# ratatouille.net
KiCad netlist of a schematic drawn in EAGLE
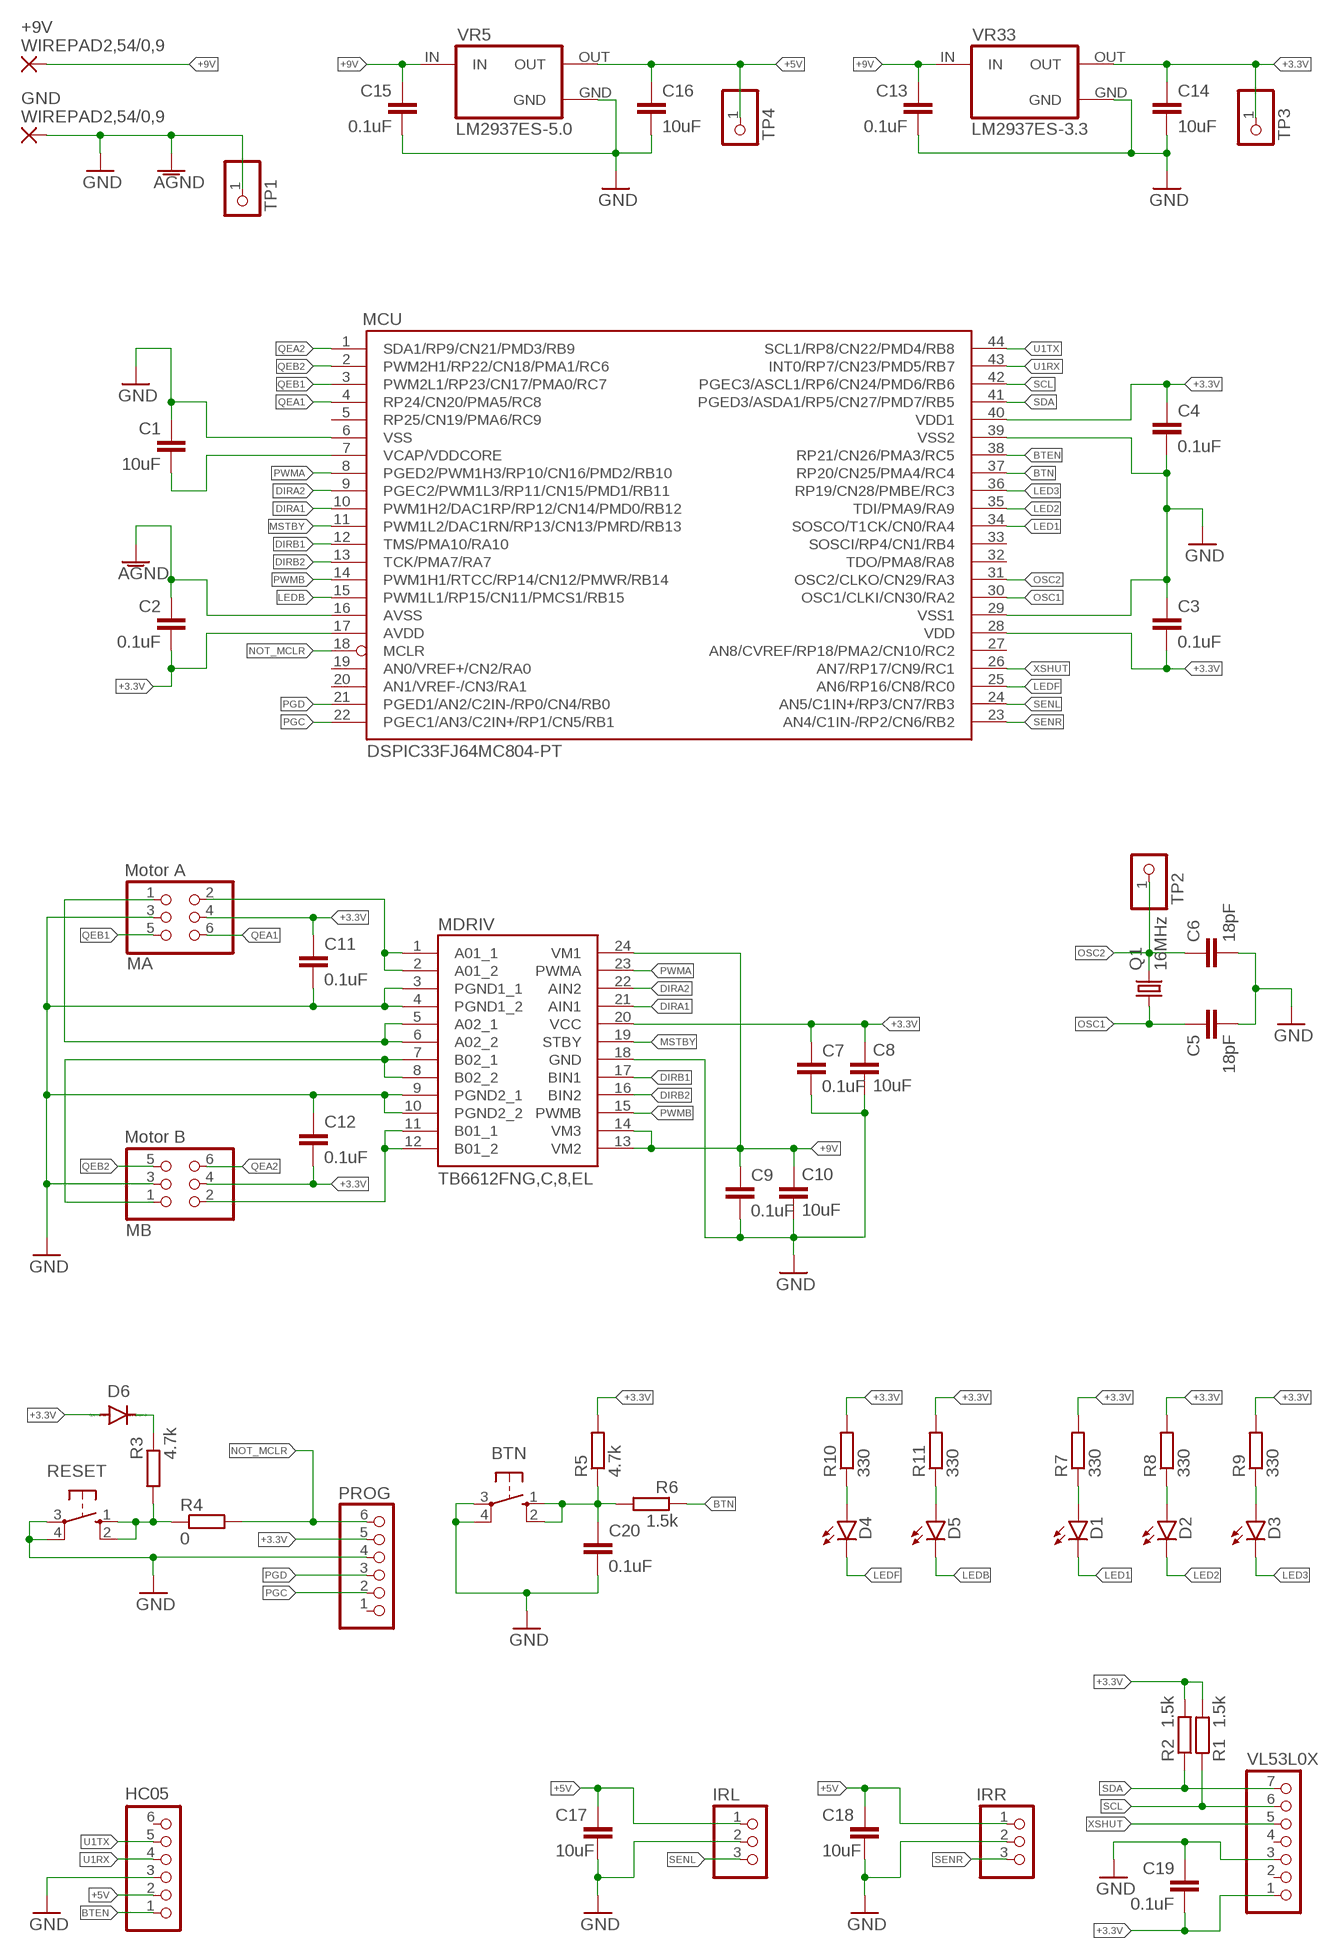
[diagram p0: schematic, sheet 1]

(export (version "E")
  (design (tool "Eeschema 10.0.6"))
  (components
    (comp (ref "+9V")
      (value "WIREPAD2,54/0,9")
      (footprint "eagle-import:2,54_0,9")
      (libsource (lib "eagle-import") (part "WIREPAD2,54/0,9"))
    )
    (comp (ref "BTN")
      (value "10-XX")
      (footprint "eagle-import:B3F-10XX")
      (fields (field (name "MPN") "B3F-1000"))
      (libsource (lib "eagle-import") (part "10-XX"))
    )
    (comp (ref "C1")
      (value "10uF")
      (footprint "eagle-import:C3216")
      (libsource (lib "eagle-import") (part "C-EUC3216"))
    )
    (comp (ref "C2")
      (value "0.1uF")
      (footprint "eagle-import:C0805")
      (libsource (lib "eagle-import") (part "C-EUC0805"))
    )
    (comp (ref "C3")
      (value "0.1uF")
      (footprint "eagle-import:C0805")
      (libsource (lib "eagle-import") (part "C-EUC0805"))
    )
    (comp (ref "C4")
      (value "0.1uF")
      (footprint "eagle-import:C0805")
      (libsource (lib "eagle-import") (part "C-EUC0805"))
    )
    (comp (ref "C5")
      (value "18pF")
      (footprint "eagle-import:C0805")
      (libsource (lib "eagle-import") (part "C-EUC0805"))
    )
    (comp (ref "C6")
      (value "18pF")
      (footprint "eagle-import:C0805")
      (libsource (lib "eagle-import") (part "C-EUC0805"))
    )
    (comp (ref "C7")
      (value "0.1uF")
      (footprint "eagle-import:C0805")
      (libsource (lib "eagle-import") (part "C-EUC0805"))
    )
    (comp (ref "C8")
      (value "10uF")
      (footprint "eagle-import:C3216")
      (libsource (lib "eagle-import") (part "C-EUC3216"))
    )
    (comp (ref "C9")
      (value "0.1uF")
      (footprint "eagle-import:C0805")
      (libsource (lib "eagle-import") (part "C-EUC0805"))
    )
    (comp (ref "C10")
      (value "10uF")
      (footprint "eagle-import:C3216")
      (libsource (lib "eagle-import") (part "C-EUC3216"))
    )
    (comp (ref "C11")
      (value "0.1uF")
      (footprint "eagle-import:C0805")
      (libsource (lib "eagle-import") (part "C-EUC0805"))
    )
    (comp (ref "C12")
      (value "0.1uF")
      (footprint "eagle-import:C0805")
      (libsource (lib "eagle-import") (part "C-EUC0805"))
    )
    (comp (ref "C13")
      (value "0.1uF")
      (footprint "eagle-import:C0805")
      (libsource (lib "eagle-import") (part "C-EUC0805"))
    )
    (comp (ref "C14")
      (value "10uF")
      (footprint "eagle-import:C3216")
      (libsource (lib "eagle-import") (part "C-EUC3216"))
    )
    (comp (ref "C15")
      (value "0.1uF")
      (footprint "eagle-import:C0805")
      (libsource (lib "eagle-import") (part "C-EUC0805"))
    )
    (comp (ref "C16")
      (value "10uF")
      (footprint "eagle-import:C3216")
      (libsource (lib "eagle-import") (part "C-EUC3216"))
    )
    (comp (ref "C17")
      (value "10uF")
      (footprint "eagle-import:C0805")
      (libsource (lib "eagle-import") (part "C-EUC0805"))
    )
    (comp (ref "C18")
      (value "10uF")
      (footprint "eagle-import:C0805")
      (libsource (lib "eagle-import") (part "C-EUC0805"))
    )
    (comp (ref "C19")
      (value "0.1uF")
      (footprint "eagle-import:C0805")
      (libsource (lib "eagle-import") (part "C-EUC0805"))
    )
    (comp (ref "C20")
      (value "0.1uF")
      (footprint "eagle-import:C0805")
      (libsource (lib "eagle-import") (part "C-EUC0805"))
    )
    (comp (ref "D1")
      (value "LEDCHIP-LED0805")
      (footprint "eagle-import:CHIP-LED0805")
      (libsource (lib "eagle-import") (part "LEDCHIP-LED0805"))
    )
    (comp (ref "D2")
      (value "LEDCHIP-LED0805")
      (footprint "eagle-import:CHIP-LED0805")
      (libsource (lib "eagle-import") (part "LEDCHIP-LED0805"))
    )
    (comp (ref "D3")
      (value "LEDCHIP-LED0805")
      (footprint "eagle-import:CHIP-LED0805")
      (libsource (lib "eagle-import") (part "LEDCHIP-LED0805"))
    )
    (comp (ref "D4")
      (value "LED3MM")
      (footprint "eagle-import:LED3MM")
      (libsource (lib "eagle-import") (part "LED3MM"))
    )
    (comp (ref "D5")
      (value "LED3MM")
      (footprint "eagle-import:LED3MM")
      (libsource (lib "eagle-import") (part "LED3MM"))
    )
    (comp (ref "D6")
      (value "DIODE-SOD123")
      (footprint "eagle-import:SOD123")
      (libsource (lib "eagle-import") (part "DIODE-SOD123"))
    )
    (comp (ref "GND")
      (value "WIREPAD2,54/0,9")
      (footprint "eagle-import:2,54_0,9")
      (libsource (lib "eagle-import") (part "WIREPAD2,54/0,9"))
    )
    (comp (ref "HC05")
      (value "PINHD-1X6")
      (footprint "eagle-import:1X06")
      (libsource (lib "eagle-import") (part "PINHD-1X6"))
    )
    (comp (ref "IRL")
      (value "PINHD-1X3")
      (footprint "eagle-import:1X03")
      (libsource (lib "eagle-import") (part "PINHD-1X3"))
    )
    (comp (ref "IRR")
      (value "PINHD-1X3")
      (footprint "eagle-import:1X03")
      (libsource (lib "eagle-import") (part "PINHD-1X3"))
    )
    (comp (ref "MA")
      (value "PINHD-2X3")
      (footprint "eagle-import:2X03")
      (libsource (lib "eagle-import") (part "PINHD-2X3"))
    )
    (comp (ref "MB")
      (value "PINHD-2X3")
      (footprint "eagle-import:2X03")
      (libsource (lib "eagle-import") (part "PINHD-2X3"))
    )
    (comp (ref "MCU")
      (value "DSPIC33FJ64MC804-PT")
      (footprint "eagle-import:TQFP44")
      (libsource (lib "eagle-import") (part "DSPIC33FJ64MC804-PT"))
    )
    (comp (ref "MDRIV")
      (value "TB6612FNG,C,8,EL")
      (footprint "eagle-import:SOP65P760X160-24N")
      (fields (field (name "MOUSER_PART_NUMBER") "757-TB6612FNGC8EL"))
      (libsource (lib "eagle-import") (part "TB6612FNG,C,8,EL"))
    )
    (comp (ref "PROG")
      (value "PINHD-1X6/90")
      (footprint "eagle-import:1X06_90")
      (libsource (lib "eagle-import") (part "PINHD-1X6/90"))
    )
    (comp (ref "Q1")
      (value "16MHz")
      (footprint "eagle-import:HC49U-V")
      (libsource (lib "eagle-import") (part "CRYSTALHC49U-V"))
    )
    (comp (ref "R1")
      (value "1.5k")
      (footprint "eagle-import:R0805")
      (libsource (lib "eagle-import") (part "R-EU_R0805"))
    )
    (comp (ref "R2")
      (value "1.5k")
      (footprint "eagle-import:R0805")
      (libsource (lib "eagle-import") (part "R-EU_R0805"))
    )
    (comp (ref "R3")
      (value "4.7k")
      (footprint "eagle-import:R0805")
      (libsource (lib "eagle-import") (part "R-EU_R0805"))
    )
    (comp (ref "R4")
      (value "0")
      (footprint "eagle-import:R0805")
      (libsource (lib "eagle-import") (part "R-EU_R0805"))
    )
    (comp (ref "R5")
      (value "4.7k")
      (footprint "eagle-import:R0805")
      (libsource (lib "eagle-import") (part "R-EU_R0805"))
    )
    (comp (ref "R6")
      (value "1.5k")
      (footprint "eagle-import:R0805")
      (libsource (lib "eagle-import") (part "R-EU_R0805"))
    )
    (comp (ref "R7")
      (value "330")
      (footprint "eagle-import:R0805")
      (libsource (lib "eagle-import") (part "R-EU_R0805"))
    )
    (comp (ref "R8")
      (value "330")
      (footprint "eagle-import:R0805")
      (libsource (lib "eagle-import") (part "R-EU_R0805"))
    )
    (comp (ref "R9")
      (value "330")
      (footprint "eagle-import:R0805")
      (libsource (lib "eagle-import") (part "R-EU_R0805"))
    )
    (comp (ref "R10")
      (value "330")
      (footprint "eagle-import:R0805")
      (libsource (lib "eagle-import") (part "R-EU_R0805"))
    )
    (comp (ref "R11")
      (value "330")
      (footprint "eagle-import:R0805")
      (libsource (lib "eagle-import") (part "R-EU_R0805"))
    )
    (comp (ref "RESET")
      (value "10-XX")
      (footprint "eagle-import:B3F-10XX")
      (fields (field (name "MPN") "B3F-1000"))
      (libsource (lib "eagle-import") (part "10-XX"))
    )
    (comp (ref "TP1")
      (value "PINHD-1X1")
      (footprint "eagle-import:1X01")
      (libsource (lib "eagle-import") (part "PINHD-1X1"))
    )
    (comp (ref "TP2")
      (value "PINHD-1X1")
      (footprint "eagle-import:1X01")
      (libsource (lib "eagle-import") (part "PINHD-1X1"))
    )
    (comp (ref "TP3")
      (value "PINHD-1X1")
      (footprint "eagle-import:1X01")
      (libsource (lib "eagle-import") (part "PINHD-1X1"))
    )
    (comp (ref "TP4")
      (value "PINHD-1X1")
      (footprint "eagle-import:1X01")
      (libsource (lib "eagle-import") (part "PINHD-1X1"))
    )
    (comp (ref "VL53L0X")
      (value "PINHD-1X7")
      (footprint "eagle-import:1X07")
      (libsource (lib "eagle-import") (part "PINHD-1X7"))
    )
    (comp (ref "VR5")
      (value "LM2937ES-5.0")
      (footprint "eagle-import:TO263")
      (libsource (lib "eagle-import") (part "LM2937ES-5.0"))
    )
    (comp (ref "VR33")
      (value "LM2937ES-3.3")
      (footprint "eagle-import:TO263")
      (libsource (lib "eagle-import") (part "LM2937ES-3.3"))
    )
  )
  (nets
    (net (code "1") (name "+3.3V") (class "Default")
      (node (ref "C11") (pin "2") (pinfunction "2_2") (pintype "passive"))
      (node (ref "C12") (pin "2") (pinfunction "2_2") (pintype "passive"))
      (node (ref "C14") (pin "1") (pinfunction "1_1") (pintype "passive"))
      (node (ref "C19") (pin "1") (pinfunction "1_1") (pintype "passive"))
      (node (ref "C2") (pin "1") (pinfunction "1_1") (pintype "passive"))
      (node (ref "C3") (pin "1") (pinfunction "1_1") (pintype "passive"))
      (node (ref "C4") (pin "1") (pinfunction "1_1") (pintype "passive"))
      (node (ref "C7") (pin "1") (pinfunction "1_1") (pintype "passive"))
      (node (ref "C8") (pin "1") (pinfunction "1_1") (pintype "passive"))
      (node (ref "D6") (pin "A") (pinfunction "A_A") (pintype "passive"))
      (node (ref "MA") (pin "4") (pinfunction "4_4") (pintype "passive"))
      (node (ref "MB") (pin "4") (pinfunction "4_4") (pintype "passive"))
      (node (ref "MCU") (pin "17") (pinfunction "AVDD_17") (pintype "power_in"))
      (node (ref "MCU") (pin "28") (pinfunction "VDD_28") (pintype "power_in"))
      (node (ref "MCU") (pin "40") (pinfunction "VDD1_40") (pintype "power_in"))
      (node (ref "MDRIV") (pin "20") (pinfunction "VCC_20") (pintype "power_in"))
      (node (ref "PROG") (pin "5") (pinfunction "5_5") (pintype "passive"))
      (node (ref "R1") (pin "2") (pinfunction "2_2") (pintype "passive"))
      (node (ref "R10") (pin "2") (pinfunction "2_2") (pintype "passive"))
      (node (ref "R11") (pin "2") (pinfunction "2_2") (pintype "passive"))
      (node (ref "R2") (pin "2") (pinfunction "2_2") (pintype "passive"))
      (node (ref "R5") (pin "2") (pinfunction "2_2") (pintype "passive"))
      (node (ref "R7") (pin "2") (pinfunction "2_2") (pintype "passive"))
      (node (ref "R8") (pin "2") (pinfunction "2_2") (pintype "passive"))
      (node (ref "R9") (pin "2") (pinfunction "2_2") (pintype "passive"))
      (node (ref "TP3") (pin "1") (pinfunction "1_1") (pintype "passive"))
      (node (ref "VL53L0X") (pin "1") (pinfunction "1_1") (pintype "passive"))
      (node (ref "VR33") (pin "OUT") (pinfunction "OUT_OUT") (pintype "output"))
    )
    (net (code "2") (name "+5V") (class "Default")
      (node (ref "C16") (pin "1") (pinfunction "1_1") (pintype "passive"))
      (node (ref "C17") (pin "1") (pinfunction "1_1") (pintype "passive"))
      (node (ref "C18") (pin "1") (pinfunction "1_1") (pintype "passive"))
      (node (ref "HC05") (pin "2") (pinfunction "2_2") (pintype "passive"))
      (node (ref "IRL") (pin "1") (pinfunction "1_1") (pintype "passive"))
      (node (ref "IRR") (pin "1") (pinfunction "1_1") (pintype "passive"))
      (node (ref "TP4") (pin "1") (pinfunction "1_1") (pintype "passive"))
      (node (ref "VR5") (pin "OUT") (pinfunction "OUT_OUT") (pintype "output"))
    )
    (net (code "3") (name "+9V") (class "Default")
      (node (ref "+9V") (pin "1") (pinfunction "P_1") (pintype "passive"))
      (node (ref "C10") (pin "1") (pinfunction "1_1") (pintype "passive"))
      (node (ref "C13") (pin "1") (pinfunction "1_1") (pintype "passive"))
      (node (ref "C15") (pin "1") (pinfunction "1_1") (pintype "passive"))
      (node (ref "C9") (pin "1") (pinfunction "1_1") (pintype "passive"))
      (node (ref "MDRIV") (pin "13") (pinfunction "VM2_13") (pintype "bidirectional"))
      (node (ref "MDRIV") (pin "14") (pinfunction "VM3_14") (pintype "bidirectional"))
      (node (ref "MDRIV") (pin "24") (pinfunction "VM1_24") (pintype "bidirectional"))
      (node (ref "VR33") (pin "IN") (pinfunction "IN_IN") (pintype "input"))
      (node (ref "VR5") (pin "IN") (pinfunction "IN_IN") (pintype "input"))
    )
    (net (code "4") (name "AGND") (class "Default")
      (node (ref "BTN") (pin "3") (pinfunction "P_3") (pintype "passive"))
      (node (ref "BTN") (pin "4") (pinfunction "P1_4") (pintype "passive"))
      (node (ref "C1") (pin "2") (pinfunction "2_2") (pintype "passive"))
      (node (ref "C10") (pin "2") (pinfunction "2_2") (pintype "passive"))
      (node (ref "C11") (pin "1") (pinfunction "1_1") (pintype "passive"))
      (node (ref "C12") (pin "1") (pinfunction "1_1") (pintype "passive"))
      (node (ref "C13") (pin "2") (pinfunction "2_2") (pintype "passive"))
      (node (ref "C14") (pin "2") (pinfunction "2_2") (pintype "passive"))
      (node (ref "C15") (pin "2") (pinfunction "2_2") (pintype "passive"))
      (node (ref "C16") (pin "2") (pinfunction "2_2") (pintype "passive"))
      (node (ref "C17") (pin "2") (pinfunction "2_2") (pintype "passive"))
      (node (ref "C18") (pin "2") (pinfunction "2_2") (pintype "passive"))
      (node (ref "C19") (pin "2") (pinfunction "2_2") (pintype "passive"))
      (node (ref "C2") (pin "2") (pinfunction "2_2") (pintype "passive"))
      (node (ref "C20") (pin "2") (pinfunction "2_2") (pintype "passive"))
      (node (ref "C3") (pin "2") (pinfunction "2_2") (pintype "passive"))
      (node (ref "C4") (pin "2") (pinfunction "2_2") (pintype "passive"))
      (node (ref "C5") (pin "1") (pinfunction "1_1") (pintype "passive"))
      (node (ref "C6") (pin "1") (pinfunction "1_1") (pintype "passive"))
      (node (ref "C7") (pin "2") (pinfunction "2_2") (pintype "passive"))
      (node (ref "C8") (pin "2") (pinfunction "2_2") (pintype "passive"))
      (node (ref "C9") (pin "2") (pinfunction "2_2") (pintype "passive"))
      (node (ref "GND") (pin "1") (pinfunction "P_1") (pintype "passive"))
      (node (ref "HC05") (pin "3") (pinfunction "3_3") (pintype "passive"))
      (node (ref "IRL") (pin "2") (pinfunction "2_2") (pintype "passive"))
      (node (ref "IRR") (pin "2") (pinfunction "2_2") (pintype "passive"))
      (node (ref "MA") (pin "3") (pinfunction "3_3") (pintype "passive"))
      (node (ref "MB") (pin "3") (pinfunction "3_3") (pintype "passive"))
      (node (ref "MCU") (pin "16") (pinfunction "AVSS_16") (pintype "power_in"))
      (node (ref "MCU") (pin "29") (pinfunction "VSS1_29") (pintype "power_in"))
      (node (ref "MCU") (pin "39") (pinfunction "VSS2_39") (pintype "power_in"))
      (node (ref "MCU") (pin "6") (pinfunction "VSS_6") (pintype "power_in"))
      (node (ref "MDRIV") (pin "10") (pinfunction "PGND2_2_10") (pintype "power_in"))
      (node (ref "MDRIV") (pin "18") (pinfunction "GND_18") (pintype "power_in"))
      (node (ref "MDRIV") (pin "3") (pinfunction "PGND1_1_3") (pintype "power_in"))
      (node (ref "MDRIV") (pin "4") (pinfunction "PGND1_2_4") (pintype "power_in"))
      (node (ref "MDRIV") (pin "9") (pinfunction "PGND2_1_9") (pintype "power_in"))
      (node (ref "PROG") (pin "4") (pinfunction "4_4") (pintype "passive"))
      (node (ref "RESET") (pin "3") (pinfunction "P_3") (pintype "passive"))
      (node (ref "RESET") (pin "4") (pinfunction "P1_4") (pintype "passive"))
      (node (ref "TP1") (pin "1") (pinfunction "1_1") (pintype "passive"))
      (node (ref "VL53L0X") (pin "3") (pinfunction "3_3") (pintype "passive"))
      (node (ref "VR33") (pin "GND") (pinfunction "GND_GND") (pintype "power_in"))
      (node (ref "VR5") (pin "GND") (pinfunction "GND_GND") (pintype "power_in"))
    )
    (net (code "5") (name "BTEN") (class "Default")
      (node (ref "HC05") (pin "1") (pinfunction "1_1") (pintype "passive"))
      (node (ref "MCU") (pin "38") (pinfunction "RP21/CN26/PMA3/RC5_38") (pintype "bidirectional"))
    )
    (net (code "6") (name "BTN") (class "Default")
      (node (ref "MCU") (pin "37") (pinfunction "RP20/CN25/PMA4/RC4_37") (pintype "bidirectional"))
      (node (ref "R6") (pin "1") (pinfunction "1_1") (pintype "passive"))
    )
    (net (code "7") (name "DIRA1") (class "Default")
      (node (ref "MCU") (pin "10") (pinfunction "PWM1H2/DAC1RP/RP12/CN14/PMD0/RB12_10") (pintype "bidirectional"))
      (node (ref "MDRIV") (pin "21") (pinfunction "AIN1_21") (pintype "input"))
    )
    (net (code "8") (name "DIRA2") (class "Default")
      (node (ref "MCU") (pin "9") (pinfunction "PGEC2/PWM1L3/RP11/CN15/PMD1/RB11_9") (pintype "bidirectional"))
      (node (ref "MDRIV") (pin "22") (pinfunction "AIN2_22") (pintype "input"))
    )
    (net (code "9") (name "DIRB1") (class "Default")
      (node (ref "MCU") (pin "12") (pinfunction "TMS/PMA10/RA10_12") (pintype "bidirectional"))
      (node (ref "MDRIV") (pin "17") (pinfunction "BIN1_17") (pintype "input"))
    )
    (net (code "10") (name "DIRB2") (class "Default")
      (node (ref "MCU") (pin "13") (pinfunction "TCK/PMA7/RA7_13") (pintype "bidirectional"))
      (node (ref "MDRIV") (pin "16") (pinfunction "BIN2_16") (pintype "input"))
    )
    (net (code "11") (name "LED1") (class "Default")
      (node (ref "D1") (pin "C") (pinfunction "C_C") (pintype "passive"))
      (node (ref "MCU") (pin "34") (pinfunction "SOSCO/T1CK/CN0/RA4_34") (pintype "bidirectional"))
    )
    (net (code "12") (name "LED2") (class "Default")
      (node (ref "D2") (pin "C") (pinfunction "C_C") (pintype "passive"))
      (node (ref "MCU") (pin "35") (pinfunction "TDI/PMA9/RA9_35") (pintype "bidirectional"))
    )
    (net (code "13") (name "LED3") (class "Default")
      (node (ref "D3") (pin "C") (pinfunction "C_C") (pintype "passive"))
      (node (ref "MCU") (pin "36") (pinfunction "RP19/CN28/PMBE/RC3_36") (pintype "bidirectional"))
    )
    (net (code "14") (name "LEDB") (class "Default")
      (node (ref "D5") (pin "K") (pinfunction "C_K") (pintype "passive"))
      (node (ref "MCU") (pin "15") (pinfunction "PWM1L1/RP15/CN11/PMCS1/RB15_15") (pintype "bidirectional"))
    )
    (net (code "15") (name "LEDF") (class "Default")
      (node (ref "D4") (pin "K") (pinfunction "C_K") (pintype "passive"))
      (node (ref "MCU") (pin "25") (pinfunction "AN6/RP16/CN8/RC0_25") (pintype "bidirectional"))
    )
    (net (code "16") (name "MSTBY") (class "Default")
      (node (ref "MCU") (pin "11") (pinfunction "PWM1L2/DAC1RN/RP13/CN13/PMRD/RB13_11") (pintype "bidirectional"))
      (node (ref "MDRIV") (pin "19") (pinfunction "STBY_19") (pintype "bidirectional"))
    )
    (net (code "17") (name "NOT_MCLR") (class "Default")
      (node (ref "MCU") (pin "18") (pinfunction "MCLR_18") (pintype "input"))
      (node (ref "PROG") (pin "6") (pinfunction "6_6") (pintype "passive"))
      (node (ref "R4") (pin "2") (pinfunction "2_2") (pintype "passive"))
    )
    (net (code "18") (name "Net-(BTN-S)") (class "Default")
      (node (ref "BTN") (pin "1") (pinfunction "S_1") (pintype "passive"))
      (node (ref "BTN") (pin "2") (pinfunction "S1_2") (pintype "passive"))
      (node (ref "C20") (pin "1") (pinfunction "1_1") (pintype "passive"))
      (node (ref "R5") (pin "1") (pinfunction "1_1") (pintype "passive"))
      (node (ref "R6") (pin "2") (pinfunction "2_2") (pintype "passive"))
    )
    (net (code "19") (name "Net-(D1-PadA)") (class "Default")
      (node (ref "D1") (pin "A") (pinfunction "A_A") (pintype "passive"))
      (node (ref "R7") (pin "1") (pinfunction "1_1") (pintype "passive"))
    )
    (net (code "20") (name "Net-(D2-PadA)") (class "Default")
      (node (ref "D2") (pin "A") (pinfunction "A_A") (pintype "passive"))
      (node (ref "R8") (pin "1") (pinfunction "1_1") (pintype "passive"))
    )
    (net (code "21") (name "Net-(D3-PadA)") (class "Default")
      (node (ref "D3") (pin "A") (pinfunction "A_A") (pintype "passive"))
      (node (ref "R9") (pin "1") (pinfunction "1_1") (pintype "passive"))
    )
    (net (code "22") (name "Net-(D4-PadA)") (class "Default")
      (node (ref "D4") (pin "A") (pinfunction "A_A") (pintype "passive"))
      (node (ref "R10") (pin "1") (pinfunction "1_1") (pintype "passive"))
    )
    (net (code "23") (name "Net-(D5-PadA)") (class "Default")
      (node (ref "D5") (pin "A") (pinfunction "A_A") (pintype "passive"))
      (node (ref "R11") (pin "1") (pinfunction "1_1") (pintype "passive"))
    )
    (net (code "24") (name "Net-(D6-PadC)") (class "Default")
      (node (ref "D6") (pin "C") (pinfunction "C_C") (pintype "passive"))
      (node (ref "R3") (pin "2") (pinfunction "2_2") (pintype "passive"))
    )
    (net (code "25") (name "Net-(MCU-VCAP{slash}VDDCORE)") (class "Default")
      (node (ref "C1") (pin "1") (pinfunction "1_1") (pintype "passive"))
      (node (ref "MCU") (pin "7") (pinfunction "VCAP/VDDCORE_7") (pintype "power_in"))
    )
    (net (code "26") (name "Net-(MDRIV-A01_1)") (class "Default")
      (node (ref "MA") (pin "2") (pinfunction "2_2") (pintype "passive"))
      (node (ref "MDRIV") (pin "1") (pinfunction "A01_1_1") (pintype "bidirectional"))
      (node (ref "MDRIV") (pin "2") (pinfunction "A01_2_2") (pintype "bidirectional"))
    )
    (net (code "27") (name "Net-(MDRIV-A02_1)") (class "Default")
      (node (ref "MA") (pin "1") (pinfunction "1_1") (pintype "passive"))
      (node (ref "MDRIV") (pin "5") (pinfunction "A02_1_5") (pintype "bidirectional"))
      (node (ref "MDRIV") (pin "6") (pinfunction "A02_2_6") (pintype "bidirectional"))
    )
    (net (code "28") (name "Net-(MDRIV-B01_1)") (class "Default")
      (node (ref "MB") (pin "2") (pinfunction "2_2") (pintype "passive"))
      (node (ref "MDRIV") (pin "11") (pinfunction "B01_1_11") (pintype "bidirectional"))
      (node (ref "MDRIV") (pin "12") (pinfunction "B01_2_12") (pintype "bidirectional"))
    )
    (net (code "29") (name "Net-(MDRIV-B02_1)") (class "Default")
      (node (ref "MB") (pin "1") (pinfunction "1_1") (pintype "passive"))
      (node (ref "MDRIV") (pin "7") (pinfunction "B02_1_7") (pintype "bidirectional"))
      (node (ref "MDRIV") (pin "8") (pinfunction "B02_2_8") (pintype "bidirectional"))
    )
    (net (code "30") (name "Net-(RESET-S)") (class "Default")
      (node (ref "R3") (pin "1") (pinfunction "1_1") (pintype "passive"))
      (node (ref "R4") (pin "1") (pinfunction "1_1") (pintype "passive"))
      (node (ref "RESET") (pin "1") (pinfunction "S_1") (pintype "passive"))
      (node (ref "RESET") (pin "2") (pinfunction "S1_2") (pintype "passive"))
    )
    (net (code "31") (name "OSC1") (class "Default")
      (node (ref "C5") (pin "2") (pinfunction "2_2") (pintype "passive"))
      (node (ref "MCU") (pin "30") (pinfunction "OSC1/CLKI/CN30/RA2_30") (pintype "bidirectional"))
      (node (ref "Q1") (pin "1") (pinfunction "1_1") (pintype "passive"))
    )
    (net (code "32") (name "OSC2") (class "Default")
      (node (ref "C6") (pin "2") (pinfunction "2_2") (pintype "passive"))
      (node (ref "MCU") (pin "31") (pinfunction "OSC2/CLKO/CN29/RA3_31") (pintype "bidirectional"))
      (node (ref "Q1") (pin "2") (pinfunction "2_2") (pintype "passive"))
      (node (ref "TP2") (pin "1") (pinfunction "1_1") (pintype "passive"))
    )
    (net (code "33") (name "PGC") (class "Default")
      (node (ref "MCU") (pin "22") (pinfunction "PGEC1/AN3/C2IN+/RP1/CN5/RB1_22") (pintype "bidirectional"))
      (node (ref "PROG") (pin "2") (pinfunction "2_2") (pintype "passive"))
    )
    (net (code "34") (name "PGD") (class "Default")
      (node (ref "MCU") (pin "21") (pinfunction "PGED1/AN2/C2IN-/RP0/CN4/RB0_21") (pintype "bidirectional"))
      (node (ref "PROG") (pin "3") (pinfunction "3_3") (pintype "passive"))
    )
    (net (code "35") (name "PWMA") (class "Default")
      (node (ref "MCU") (pin "8") (pinfunction "PGED2/PWM1H3/RP10/CN16/PMD2/RB10_8") (pintype "bidirectional"))
      (node (ref "MDRIV") (pin "23") (pinfunction "PWMA_23") (pintype "bidirectional"))
    )
    (net (code "36") (name "PWMB") (class "Default")
      (node (ref "MCU") (pin "14") (pinfunction "PWM1H1/RTCC/RP14/CN12/PMWR/RB14_14") (pintype "bidirectional"))
      (node (ref "MDRIV") (pin "15") (pinfunction "PWMB_15") (pintype "bidirectional"))
    )
    (net (code "37") (name "QEA1") (class "Default")
      (node (ref "MA") (pin "6") (pinfunction "6_6") (pintype "passive"))
      (node (ref "MCU") (pin "4") (pinfunction "RP24/CN20/PMA5/RC8_4") (pintype "bidirectional"))
    )
    (net (code "38") (name "QEA2") (class "Default")
      (node (ref "MB") (pin "6") (pinfunction "6_6") (pintype "passive"))
      (node (ref "MCU") (pin "1") (pinfunction "SDA1/RP9/CN21/PMD3/RB9_1") (pintype "bidirectional"))
    )
    (net (code "39") (name "QEB1") (class "Default")
      (node (ref "MA") (pin "5") (pinfunction "5_5") (pintype "passive"))
      (node (ref "MCU") (pin "3") (pinfunction "PWM2L1/RP23/CN17/PMA0/RC7_3") (pintype "bidirectional"))
    )
    (net (code "40") (name "QEB2") (class "Default")
      (node (ref "MB") (pin "5") (pinfunction "5_5") (pintype "passive"))
      (node (ref "MCU") (pin "2") (pinfunction "PWM2H1/RP22/CN18/PMA1/RC6_2") (pintype "bidirectional"))
    )
    (net (code "41") (name "SCL") (class "Default")
      (node (ref "MCU") (pin "42") (pinfunction "PGEC3/ASCL1/RP6/CN24/PMD6/RB6_42") (pintype "bidirectional"))
      (node (ref "R1") (pin "1") (pinfunction "1_1") (pintype "passive"))
      (node (ref "VL53L0X") (pin "6") (pinfunction "6_6") (pintype "passive"))
    )
    (net (code "42") (name "SDA") (class "Default")
      (node (ref "MCU") (pin "41") (pinfunction "PGED3/ASDA1/RP5/CN27/PMD7/RB5_41") (pintype "bidirectional"))
      (node (ref "R2") (pin "1") (pinfunction "1_1") (pintype "passive"))
      (node (ref "VL53L0X") (pin "7") (pinfunction "7_7") (pintype "passive"))
    )
    (net (code "43") (name "SENL") (class "Default")
      (node (ref "IRL") (pin "3") (pinfunction "3_3") (pintype "passive"))
      (node (ref "MCU") (pin "24") (pinfunction "AN5/C1IN+/RP3/CN7/RB3_24") (pintype "bidirectional"))
    )
    (net (code "44") (name "SENR") (class "Default")
      (node (ref "IRR") (pin "3") (pinfunction "3_3") (pintype "passive"))
      (node (ref "MCU") (pin "23") (pinfunction "AN4/C1IN-/RP2/CN6/RB2_23") (pintype "bidirectional"))
    )
    (net (code "45") (name "U1RX") (class "Default")
      (node (ref "HC05") (pin "4") (pinfunction "4_4") (pintype "passive"))
      (node (ref "MCU") (pin "43") (pinfunction "INT0/RP7/CN23/PMD5/RB7_43") (pintype "bidirectional"))
    )
    (net (code "46") (name "U1TX") (class "Default")
      (node (ref "HC05") (pin "5") (pinfunction "5_5") (pintype "passive"))
      (node (ref "MCU") (pin "44") (pinfunction "SCL1/RP8/CN22/PMD4/RB8_44") (pintype "bidirectional"))
    )
    (net (code "47") (name "XSHUT") (class "Default")
      (node (ref "MCU") (pin "26") (pinfunction "AN7/RP17/CN9/RC1_26") (pintype "bidirectional"))
      (node (ref "VL53L0X") (pin "5") (pinfunction "5_5") (pintype "passive"))
    )
    (net (code "48") (name "unconnected-(HC05-Pad6)") (class "Default")
      (node (ref "HC05") (pin "6") (pinfunction "6_6") (pintype "passive"))
    )
    (net (code "49") (name "unconnected-(MCU-AN0{slash}VREF+{slash}CN2{slash}RA0-Pad19)") (class "Default")
      (node (ref "MCU") (pin "19") (pinfunction "AN0/VREF+/CN2/RA0_19") (pintype "bidirectional"))
    )
    (net (code "50") (name "unconnected-(MCU-AN1{slash}VREF-{slash}CN3{slash}RA1-Pad20)") (class "Default")
      (node (ref "MCU") (pin "20") (pinfunction "AN1/VREF-/CN3/RA1_20") (pintype "bidirectional"))
    )
    (net (code "51") (name "unconnected-(MCU-AN8{slash}CVREF{slash}RP18{slash}PMA2{slash}CN10{slash}RC2-Pad27)") (class "Default")
      (node (ref "MCU") (pin "27") (pinfunction "AN8/CVREF/RP18/PMA2/CN10/RC2_27") (pintype "bidirectional"))
    )
    (net (code "52") (name "unconnected-(MCU-RP25{slash}CN19{slash}PMA6{slash}RC9-Pad5)") (class "Default")
      (node (ref "MCU") (pin "5") (pinfunction "RP25/CN19/PMA6/RC9_5") (pintype "bidirectional"))
    )
    (net (code "53") (name "unconnected-(MCU-SOSCI{slash}RP4{slash}CN1{slash}RB4-Pad33)") (class "Default")
      (node (ref "MCU") (pin "33") (pinfunction "SOSCI/RP4/CN1/RB4_33") (pintype "bidirectional"))
    )
    (net (code "54") (name "unconnected-(MCU-TDO{slash}PMA8{slash}RA8-Pad32)") (class "Default")
      (node (ref "MCU") (pin "32") (pinfunction "TDO/PMA8/RA8_32") (pintype "bidirectional"))
    )
    (net (code "55") (name "unconnected-(PROG-Pad1)") (class "Default")
      (node (ref "PROG") (pin "1") (pinfunction "1_1") (pintype "passive"))
    )
    (net (code "56") (name "unconnected-(VL53L0X-Pad2)") (class "Default")
      (node (ref "VL53L0X") (pin "2") (pinfunction "2_2") (pintype "passive"))
    )
    (net (code "57") (name "unconnected-(VL53L0X-Pad4)") (class "Default")
      (node (ref "VL53L0X") (pin "4") (pinfunction "4_4") (pintype "passive"))
    )
  )
)
